# 09sata.net
KiCad netlist of a schematic drawn in Altium Designer
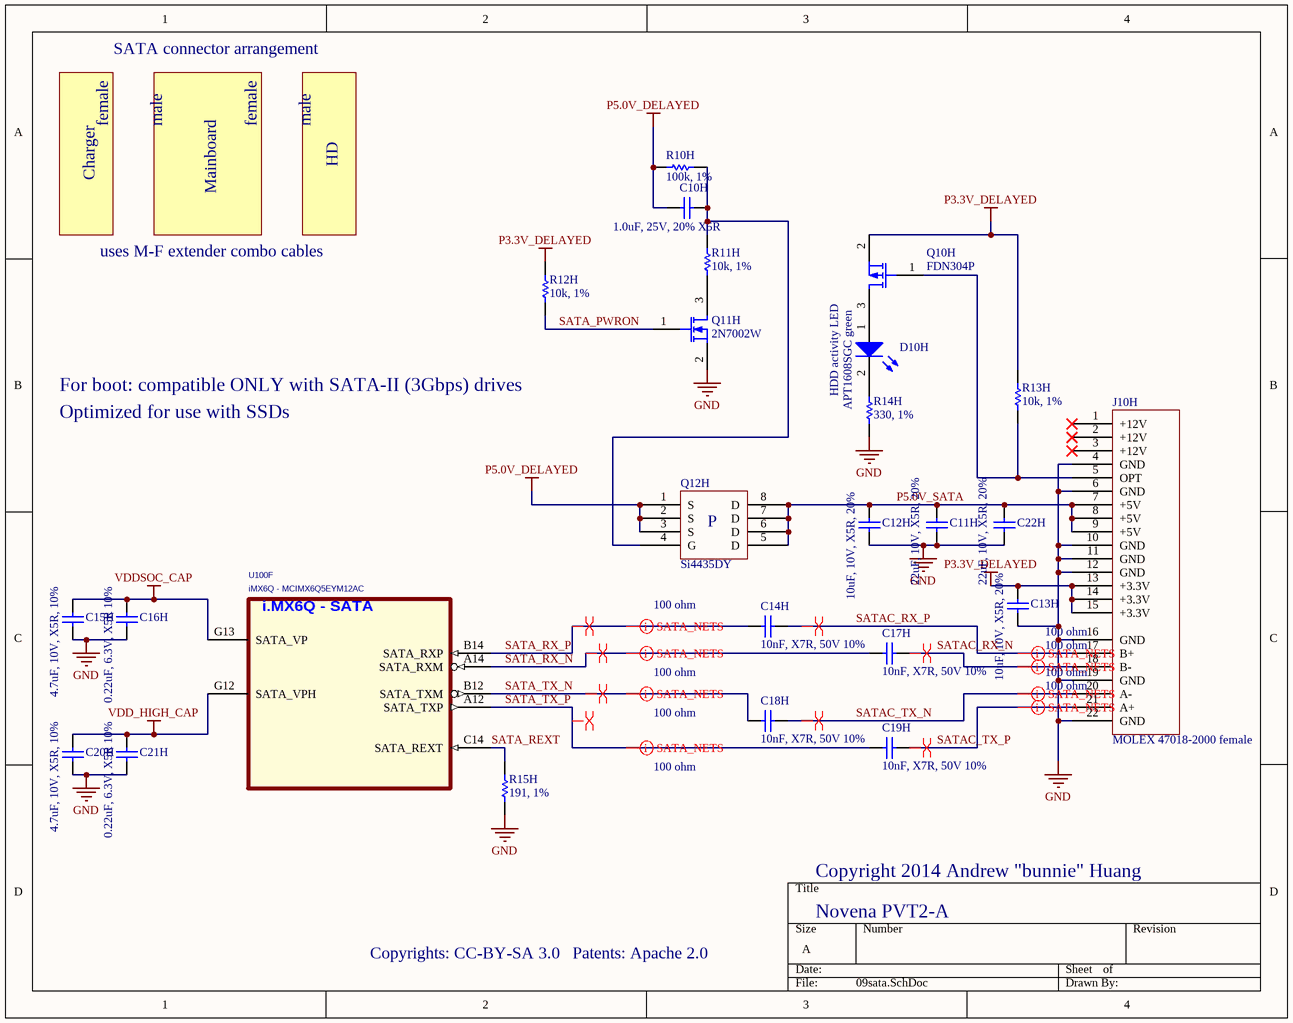
[diagram p0: 09sata.SchDoc]

(export (version "E")
  (design (tool "Eeschema 10.0.6"))
  (components
    (comp (ref "C10H")
      (value "1.0uF, 25V, 20% X5R")
      (footprint "CAPC1608N")
      (description "Capacitor (Semiconductor SIM Model)")
      (fields (field (name "PUBLISHER") "Altium Limited"))
      (libsource (lib "Miscellaneous Devices") (part "Cap Semi"))
    )
    (comp (ref "C11H")
      (value "22uF, 10V, X5R, 20%")
      (footprint "CAPC2012N")
      (description "Capacitor (Semiconductor SIM Model)")
      (fields (field (name "PUBLISHER") "Altium Limited"))
      (libsource (lib "Miscellaneous Devices") (part "Cap Semi"))
    )
    (comp (ref "C12H")
      (value "10uF, 10V, X5R, 20%")
      (footprint "CAPC1608N")
      (description "Capacitor (Semiconductor SIM Model)")
      (fields (field (name "PUBLISHER") "Altium Limited"))
      (libsource (lib "Miscellaneous Devices") (part "Cap Semi"))
    )
    (comp (ref "C13H")
      (value "10uF, 10V, X5R, 20%")
      (footprint "CAPC1608N")
      (description "Capacitor (Semiconductor SIM Model)")
      (fields (field (name "PUBLISHER") "Altium Limited"))
      (libsource (lib "Miscellaneous Devices") (part "Cap Semi"))
    )
    (comp (ref "C14H")
      (value "10nF, X7R, 50V 10%")
      (footprint "CAPC1005N")
      (description "Capacitor (Semiconductor SIM Model)")
      (fields (field (name "PUBLISHER") "Altium Limited"))
      (libsource (lib "Miscellaneous Devices") (part "Cap Semi"))
    )
    (comp (ref "C15H")
      (value "4.7uF, 10V, X5R, 10%")
      (footprint "CAPC1608N_HD")
      (description "Capacitor (Semiconductor SIM Model)")
      (fields (field (name "PUBLISHER") "Altium Limited"))
      (libsource (lib "Miscellaneous Devices") (part "Cap Semi"))
    )
    (comp (ref "C16H")
      (value "0.22uF, 6.3V, X5R 10%")
      (footprint "CAPC0603N_B")
      (description "CAP CER 0.22UF 6.3V 20% X5R 0201")
      (fields (field (name "PUBLISHER") "Altium Limited"))
      (libsource (lib "Miscellaneous Devices") (part "Cap Semi"))
    )
    (comp (ref "C17H")
      (value "10nF, X7R, 50V 10%")
      (footprint "CAPC1005N")
      (description "Capacitor (Semiconductor SIM Model)")
      (fields (field (name "PUBLISHER") "Altium Limited"))
      (libsource (lib "Miscellaneous Devices") (part "Cap Semi"))
    )
    (comp (ref "C18H")
      (value "10nF, X7R, 50V 10%")
      (footprint "CAPC1005N")
      (description "Capacitor (Semiconductor SIM Model)")
      (fields (field (name "PUBLISHER") "Altium Limited"))
      (libsource (lib "Miscellaneous Devices") (part "Cap Semi"))
    )
    (comp (ref "C19H")
      (value "10nF, X7R, 50V 10%")
      (footprint "CAPC1005N")
      (description "Capacitor (Semiconductor SIM Model)")
      (fields (field (name "PUBLISHER") "Altium Limited"))
      (libsource (lib "Miscellaneous Devices") (part "Cap Semi"))
    )
    (comp (ref "C20H")
      (value "4.7uF, 10V, X5R, 10%")
      (footprint "CAPC1608N_HD")
      (description "Capacitor (Semiconductor SIM Model)")
      (fields (field (name "PUBLISHER") "Altium Limited"))
      (libsource (lib "Miscellaneous Devices") (part "Cap Semi"))
    )
    (comp (ref "C21H")
      (value "0.22uF, 6.3V, X5R 10%")
      (footprint "CAPC0603N_B")
      (description "CAP CER 0.22UF 6.3V 20% X5R 0201")
      (fields (field (name "PUBLISHER") "Altium Limited"))
      (libsource (lib "Miscellaneous Devices") (part "Cap Semi"))
    )
    (comp (ref "C22H")
      (value "22uF, 10V, X5R, 20%")
      (footprint "CAPC2012N")
      (description "Capacitor (Semiconductor SIM Model)")
      (fields (field (name "PUBLISHER") "Altium Limited"))
      (libsource (lib "Miscellaneous Devices") (part "Cap Semi"))
    )
    (comp (ref "D10H")
      (value "APT1608SGC green")
      (footprint "CD1608-0603")
      (description "Typical RED, GREEN, YELLOW, AMBER GaAs LED")
      (fields (field (name "PUBLISHER") "Altium Limited"))
      (libsource (lib "Miscellaneous Devices") (part "LED2"))
    )
    (comp (ref "J10H")
      (value "MOLEX 47018-2000 female")
      (footprint "SATA_MOLEX_47018_2000")
      (description "SATA+Power connector")
      (libsource (lib "commonsch") (part "SATA_22P_HEADER"))
    )
    (comp (ref "Q10H")
      (value "FDN304P")
      (footprint "SOT23-3N")
      (description "P-Channel MOSFET")
      (fields (field (name "PUBLISHER") "Altium Limited"))
      (libsource (lib "Miscellaneous Devices") (part "MOSFET-P"))
    )
    (comp (ref "Q11H")
      (value "2N7002W")
      (footprint "SOT323-3AN")
      (description "N-Channel MOSFET")
      (fields (field (name "PUBLISHER") "Altium Limited"))
      (libsource (lib "Miscellaneous Devices") (part "MOSFET-N"))
    )
    (comp (ref "Q12H")
      (value "Si4435DY")
      (footprint "SOIC127P600-8AN")
      (description "Singre P-channel FET, 8A, 30V")
      (libsource (lib "commonsch") (part "Si4435DY"))
    )
    (comp (ref "R10H")
      (value "100k, 1%")
      (footprint "RESC1005N")
      (description "Resistor")
      (fields (field (name "PUBLISHER") "Altium Limited"))
      (libsource (lib "Miscellaneous Devices") (part "Res1"))
    )
    (comp (ref "R11H")
      (value "10k, 1%")
      (footprint "RESC1005N")
      (description "Resistor")
      (fields (field (name "PUBLISHER") "Altium Limited"))
      (libsource (lib "Miscellaneous Devices") (part "Res1"))
    )
    (comp (ref "R12H")
      (value "10k, 1%")
      (footprint "RESC1005N")
      (description "Resistor")
      (fields (field (name "PUBLISHER") "Altium Limited"))
      (libsource (lib "Miscellaneous Devices") (part "Res1"))
    )
    (comp (ref "R13H")
      (value "10k, 1%")
      (footprint "RESC1005N")
      (description "Resistor")
      (fields (field (name "PUBLISHER") "Altium Limited"))
      (libsource (lib "Miscellaneous Devices") (part "Res1"))
    )
    (comp (ref "R14H")
      (value "330, 1%")
      (footprint "RESC1005N")
      (description "Resistor")
      (fields (field (name "PUBLISHER") "Altium Limited"))
      (libsource (lib "Miscellaneous Devices") (part "Res1"))
    )
    (comp (ref "R15H")
      (value "191, 1%")
      (footprint "RESC1005N")
      (description "Resistor")
      (fields (field (name "PUBLISHER") "Altium Limited"))
      (libsource (lib "Miscellaneous Devices") (part "Res1"))
    )
    (comp (ref "U100")
      (value "iMX6Q - MCIMX6Q5EYM12AC")
      (description "PCIMX6Q5EVT10AC")
      (libsource (lib "*") (part "PCIMX6Q6VV1A"))
    )
  )
  (nets
    (net (code "1") (name "/P5.0V_SATA") (class "Default")
      (node (ref "C11H") (pin "1") (pinfunction "1_1") (pintype "passive"))
      (node (ref "C12H") (pin "1") (pinfunction "1_1") (pintype "passive"))
      (node (ref "C22H") (pin "1") (pinfunction "1_1") (pintype "passive"))
      (node (ref "J10H") (pin "7") (pinfunction "+5V_7") (pintype "power_in"))
      (node (ref "J10H") (pin "8") (pinfunction "+5V_8") (pintype "power_in"))
      (node (ref "J10H") (pin "9") (pinfunction "+5V_9") (pintype "power_in"))
      (node (ref "Q12H") (pin "5") (pinfunction "D_5") (pintype "passive"))
      (node (ref "Q12H") (pin "6") (pinfunction "D_6") (pintype "passive"))
      (node (ref "Q12H") (pin "7") (pinfunction "D_7") (pintype "passive"))
      (node (ref "Q12H") (pin "8") (pinfunction "D_8") (pintype "passive"))
    )
    (net (code "2") (name "/SATAC_RX_N") (class "Default")
      (node (ref "C17H") (pin "2") (pinfunction "2_2") (pintype "passive"))
      (node (ref "J10H") (pin "18") (pinfunction "B-_18") (pintype "passive"))
    )
    (net (code "3") (name "/SATAC_RX_P") (class "Default")
      (node (ref "C14H") (pin "2") (pinfunction "2_2") (pintype "passive"))
      (node (ref "J10H") (pin "17") (pinfunction "B+_17") (pintype "passive"))
    )
    (net (code "4") (name "/SATAC_TX_N") (class "Default")
      (node (ref "C18H") (pin "2") (pinfunction "2_2") (pintype "passive"))
      (node (ref "J10H") (pin "20") (pinfunction "A-_20") (pintype "passive"))
    )
    (net (code "5") (name "/SATAC_TX_P") (class "Default")
      (node (ref "C19H") (pin "2") (pinfunction "2_2") (pintype "passive"))
      (node (ref "J10H") (pin "21") (pinfunction "A+_21") (pintype "passive"))
    )
    (net (code "6") (name "/SATA_PWRON") (class "Default")
      (node (ref "Q11H") (pin "1") (pinfunction "G_1") (pintype "passive"))
      (node (ref "R12H") (pin "2") (pinfunction "2_2") (pintype "passive"))
    )
    (net (code "7") (name "/SATA_REXT") (class "Default")
      (node (ref "R15H") (pin "1") (pinfunction "1_1") (pintype "passive"))
      (node (ref "U100") (pin "C14") (pinfunction "SATA_REXT_C14") (pintype "input"))
    )
    (net (code "8") (name "/SATA_RX_N") (class "Default")
      (node (ref "C17H") (pin "1") (pinfunction "1_1") (pintype "passive"))
      (node (ref "U100") (pin "A14") (pinfunction "SATA_RXM_A14") (pintype "input"))
    )
    (net (code "9") (name "/SATA_RX_P") (class "Default")
      (node (ref "C14H") (pin "1") (pinfunction "1_1") (pintype "passive"))
      (node (ref "U100") (pin "B14") (pinfunction "SATA_RXP_B14") (pintype "input"))
    )
    (net (code "10") (name "/SATA_TX_N") (class "Default")
      (node (ref "C18H") (pin "1") (pinfunction "1_1") (pintype "passive"))
      (node (ref "U100") (pin "B12") (pinfunction "SATA_TXM_B12") (pintype "output"))
    )
    (net (code "11") (name "/SATA_TX_P") (class "Default")
      (node (ref "C19H") (pin "1") (pinfunction "1_1") (pintype "passive"))
      (node (ref "U100") (pin "A12") (pinfunction "SATA_TXP_A12") (pintype "output"))
    )
    (net (code "12") (name "GND") (class "Default")
      (node (ref "C11H") (pin "2") (pinfunction "2_2") (pintype "passive"))
      (node (ref "C12H") (pin "2") (pinfunction "2_2") (pintype "passive"))
      (node (ref "C13H") (pin "2") (pinfunction "2_2") (pintype "passive"))
      (node (ref "C15H") (pin "2") (pinfunction "2_2") (pintype "passive"))
      (node (ref "C16H") (pin "2") (pinfunction "2_2") (pintype "passive"))
      (node (ref "C20H") (pin "2") (pinfunction "2_2") (pintype "passive"))
      (node (ref "C21H") (pin "2") (pinfunction "2_2") (pintype "passive"))
      (node (ref "C22H") (pin "2") (pinfunction "2_2") (pintype "passive"))
      (node (ref "J10H") (pin "10") (pinfunction "GND_10") (pintype "power_in"))
      (node (ref "J10H") (pin "11") (pinfunction "GND_11") (pintype "power_in"))
      (node (ref "J10H") (pin "12") (pinfunction "GND_12") (pintype "power_in"))
      (node (ref "J10H") (pin "16") (pinfunction "GND_16") (pintype "power_in"))
      (node (ref "J10H") (pin "19") (pinfunction "GND_19") (pintype "power_in"))
      (node (ref "J10H") (pin "22") (pinfunction "GND_22") (pintype "power_in"))
      (node (ref "J10H") (pin "4") (pinfunction "GND_4") (pintype "power_in"))
      (node (ref "J10H") (pin "6") (pinfunction "GND_6") (pintype "power_in"))
      (node (ref "Q11H") (pin "2") (pinfunction "S_2") (pintype "passive"))
      (node (ref "R14H") (pin "1") (pinfunction "1_1") (pintype "passive"))
      (node (ref "R15H") (pin "2") (pinfunction "2_2") (pintype "passive"))
    )
    (net (code "13") (name "Net-(D10H-A)") (class "Default")
      (node (ref "D10H") (pin "1") (pinfunction "A_1") (pintype "passive"))
      (node (ref "Q10H") (pin "3") (pinfunction "D_3") (pintype "passive"))
    )
    (net (code "14") (name "Net-(D10H-K)") (class "Default")
      (node (ref "D10H") (pin "2") (pinfunction "K_2") (pintype "passive"))
      (node (ref "R14H") (pin "2") (pinfunction "2_2") (pintype "passive"))
    )
    (net (code "15") (name "Net-(J10H-OPT)") (class "Default")
      (node (ref "J10H") (pin "5") (pinfunction "OPT_5") (pintype "passive"))
      (node (ref "Q10H") (pin "1") (pinfunction "G_1") (pintype "passive"))
      (node (ref "R13H") (pin "2") (pinfunction "2_2") (pintype "passive"))
    )
    (net (code "16") (name "Net-(Q11H-D)") (class "Default")
      (node (ref "Q11H") (pin "3") (pinfunction "D_3") (pintype "passive"))
      (node (ref "R11H") (pin "2") (pinfunction "2_2") (pintype "passive"))
    )
    (net (code "17") (name "Net-(Q12H-G)") (class "Default")
      (node (ref "C10H") (pin "2") (pinfunction "2_2") (pintype "passive"))
      (node (ref "Q12H") (pin "4") (pinfunction "G_4") (pintype "passive"))
      (node (ref "R10H") (pin "1") (pinfunction "1_1") (pintype "passive"))
      (node (ref "R11H") (pin "1") (pinfunction "1_1") (pintype "passive"))
    )
    (net (code "18") (name "P3.3V_DELAYED") (class "Default")
      (node (ref "C13H") (pin "1") (pinfunction "1_1") (pintype "passive"))
      (node (ref "J10H") (pin "13") (pinfunction "+3.3V_13") (pintype "power_in"))
      (node (ref "J10H") (pin "14") (pinfunction "+3.3V_14") (pintype "power_in"))
      (node (ref "J10H") (pin "15") (pinfunction "+3.3V_15") (pintype "power_in"))
      (node (ref "Q10H") (pin "2") (pinfunction "S_2") (pintype "passive"))
      (node (ref "R12H") (pin "1") (pinfunction "1_1") (pintype "passive"))
      (node (ref "R13H") (pin "1") (pinfunction "1_1") (pintype "passive"))
    )
    (net (code "19") (name "P5.0V_DELAYED") (class "Default")
      (node (ref "C10H") (pin "1") (pinfunction "1_1") (pintype "passive"))
      (node (ref "Q12H") (pin "1") (pinfunction "S_1") (pintype "passive"))
      (node (ref "Q12H") (pin "2") (pinfunction "S_2") (pintype "passive"))
      (node (ref "Q12H") (pin "3") (pinfunction "S_3") (pintype "passive"))
      (node (ref "R10H") (pin "2") (pinfunction "2_2") (pintype "passive"))
    )
    (net (code "20") (name "VDDSOC_CAP") (class "Default")
      (node (ref "C15H") (pin "1") (pinfunction "1_1") (pintype "passive"))
      (node (ref "C16H") (pin "1") (pinfunction "1_1") (pintype "passive"))
      (node (ref "U100") (pin "G13") (pinfunction "SATA_VP_G13") (pintype "power_in"))
    )
    (net (code "21") (name "VDD_HIGH_CAP") (class "Default")
      (node (ref "C20H") (pin "1") (pinfunction "1_1") (pintype "passive"))
      (node (ref "C21H") (pin "1") (pinfunction "1_1") (pintype "passive"))
      (node (ref "U100") (pin "G12") (pinfunction "SATA_VPH_G12") (pintype "power_in"))
    )
    (net (code "22") (name "unconnected-(J10H-+12V-Pad1)") (class "Default")
      (node (ref "J10H") (pin "1") (pinfunction "+12V_1") (pintype "power_in+no_connect"))
    )
    (net (code "23") (name "unconnected-(J10H-+12V-Pad2)") (class "Default")
      (node (ref "J10H") (pin "2") (pinfunction "+12V_2") (pintype "power_in+no_connect"))
    )
    (net (code "24") (name "unconnected-(J10H-+12V-Pad3)") (class "Default")
      (node (ref "J10H") (pin "3") (pinfunction "+12V_3") (pintype "power_in+no_connect"))
    )
  )
)
